# MCU.net
KiCad netlist of a schematic drawn in Altium Designer
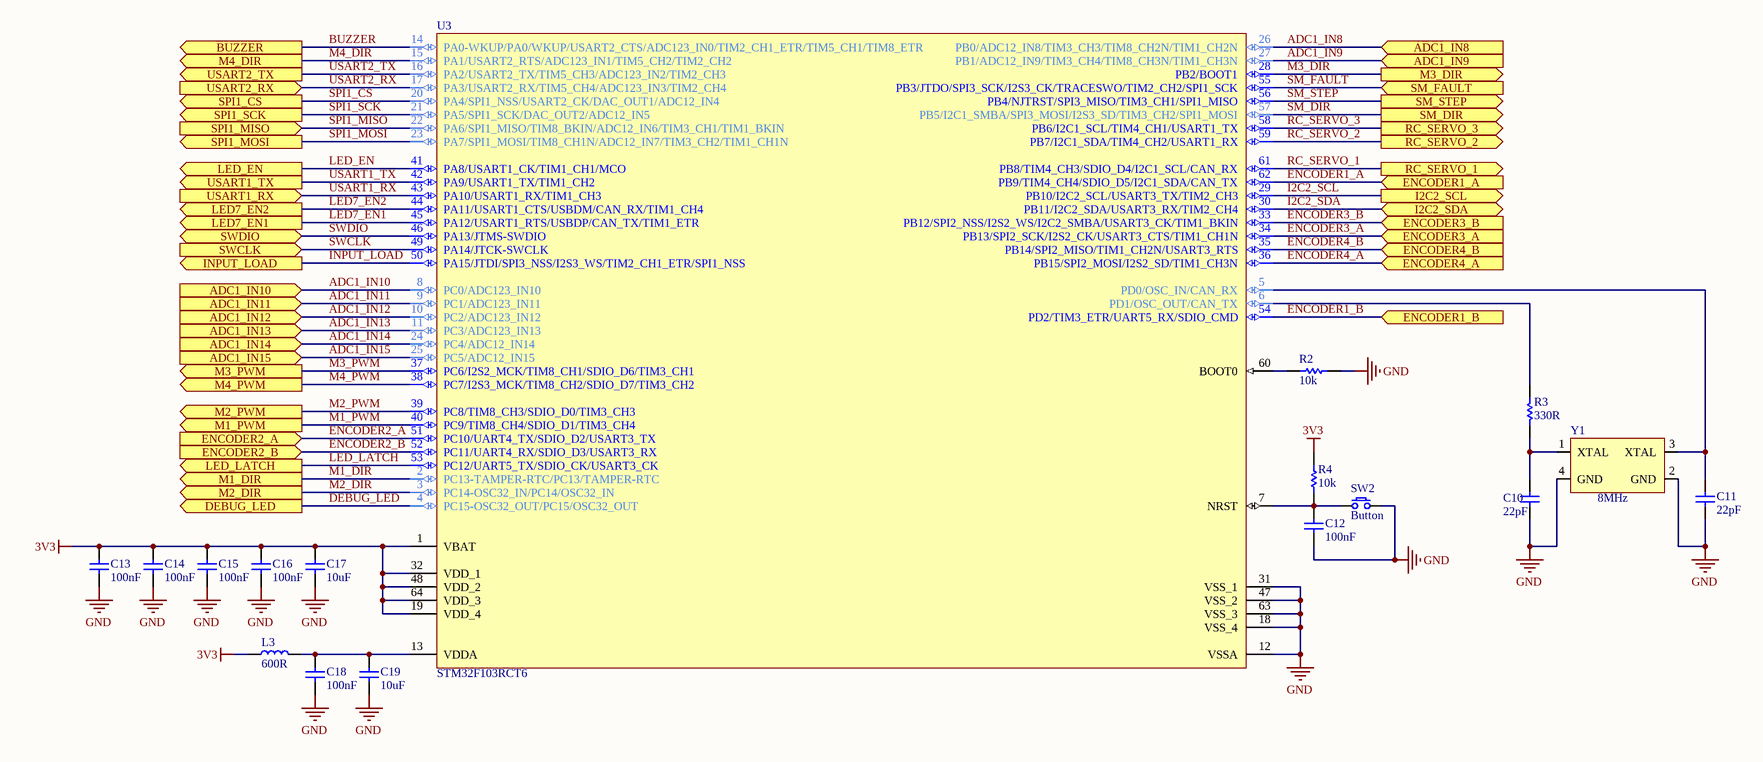
[diagram p0: MCU.SchDoc]

(export (version "E")
  (design (tool "Eeschema 10.0.6"))
  (components
    (comp (ref "C10")
      (value "22pF")
      (footprint "C 0603 (1608)")
      (description "Capacitor non-pol")
      (libsource (lib "BKIT4U_LIB") (part "Capacitor NP"))
    )
    (comp (ref "C11")
      (value "22pF")
      (footprint "C 0603 (1608)")
      (description "Capacitor non-pol")
      (libsource (lib "BKIT4U_LIB") (part "Capacitor NP"))
    )
    (comp (ref "C12")
      (value "100nF")
      (footprint "C 0603 (1608)")
      (description "Capacitor non-pol")
      (libsource (lib "BKIT4U_LIB") (part "Capacitor NP"))
    )
    (comp (ref "C13")
      (value "100nF")
      (footprint "C 0603 (1608)")
      (description "Capacitor non-pol")
      (libsource (lib "BKIT4U_LIB") (part "Capacitor NP"))
    )
    (comp (ref "C14")
      (value "100nF")
      (footprint "C 0603 (1608)")
      (description "Capacitor non-pol")
      (libsource (lib "BKIT4U_LIB") (part "Capacitor NP"))
    )
    (comp (ref "C15")
      (value "100nF")
      (footprint "C 0603 (1608)")
      (description "Capacitor non-pol")
      (libsource (lib "BKIT4U_LIB") (part "Capacitor NP"))
    )
    (comp (ref "C16")
      (value "100nF")
      (footprint "C 0603 (1608)")
      (description "Capacitor non-pol")
      (libsource (lib "BKIT4U_LIB") (part "Capacitor NP"))
    )
    (comp (ref "C17")
      (value "10uF")
      (footprint "C 0603 (1608)")
      (description "Capacitor non-pol")
      (libsource (lib "BKIT4U_LIB") (part "Capacitor NP"))
    )
    (comp (ref "C18")
      (value "100nF")
      (footprint "C 0603 (1608)")
      (description "Capacitor non-pol")
      (libsource (lib "BKIT4U_LIB") (part "Capacitor NP"))
    )
    (comp (ref "C19")
      (value "10uF")
      (footprint "C 0603 (1608)")
      (description "Capacitor non-pol")
      (libsource (lib "BKIT4U_LIB") (part "Capacitor NP"))
    )
    (comp (ref "L3")
      (value "600R")
      (footprint "L 0603 (1608)")
      (description "Inductor")
      (libsource (lib "BKIT4U_LIB") (part "Inductor"))
    )
    (comp (ref "R2")
      (value "10k")
      (footprint "R 0603 (1608)")
      (description "Resistor")
      (fields (field (name "PUBLISHER") "Altium Limited"))
      (libsource (lib "BKIT4U_LIB") (part "Resistor"))
    )
    (comp (ref "R3")
      (value "330R")
      (footprint "R 0603 (1608)")
      (description "Resistor")
      (fields (field (name "PUBLISHER") "Altium Limited"))
      (libsource (lib "BKIT4U_LIB") (part "Resistor"))
    )
    (comp (ref "R4")
      (value "10k")
      (footprint "R 0603 (1608)")
      (description "Resistor")
      (fields (field (name "PUBLISHER") "Altium Limited"))
      (libsource (lib "BKIT4U_LIB") (part "Resistor"))
    )
    (comp (ref "SW2")
      (value "Button")
      (footprint "SW/2/SMD - 6X6X5")
      (description "Tact switch 2 pin")
      (libsource (lib "BKIT4U_LIB") (part "SW SPST"))
    )
    (comp (ref "U3")
      (value "STM32F103RCT6")
      (footprint "LQFP64_N")
      (libsource (lib "BKIT4U_LIB") (part "STM32F103RCT6"))
    )
    (comp (ref "Y1")
      (value "8MHz")
      (footprint "Crystal SMD 4PIN 3225")
      (libsource (lib "BKIT4U_LIB") (part "Crystal 4pin"))
    )
  )
  (nets
    (net (code "1") (name "/ADC1_IN8") (class "Default")
      (node (ref "U3") (pin "26") (pinfunction "PB0/ADC12_IN8/TIM3_CH3/TIM8_CH2N/TIM1_CH2N_26") (pintype "bidirectional"))
    )
    (net (code "2") (name "/ADC1_IN9") (class "Default")
      (node (ref "U3") (pin "27") (pinfunction "PB1/ADC12_IN9/TIM3_CH4/TIM8_CH3N/TIM1_CH3N_27") (pintype "bidirectional"))
    )
    (net (code "3") (name "/ADC1_IN10") (class "Default")
      (node (ref "U3") (pin "8") (pinfunction "PC0/ADC123_IN10_8") (pintype "bidirectional"))
    )
    (net (code "4") (name "/ADC1_IN11") (class "Default")
      (node (ref "U3") (pin "9") (pinfunction "PC1/ADC123_IN11_9") (pintype "bidirectional"))
    )
    (net (code "5") (name "/ADC1_IN12") (class "Default")
      (node (ref "U3") (pin "10") (pinfunction "PC2/ADC123_IN12_10") (pintype "bidirectional"))
    )
    (net (code "6") (name "/ADC1_IN13") (class "Default")
      (node (ref "U3") (pin "11") (pinfunction "PC3/ADC123_IN13_11") (pintype "bidirectional"))
    )
    (net (code "7") (name "/ADC1_IN14") (class "Default")
      (node (ref "U3") (pin "24") (pinfunction "PC4/ADC12_IN14_24") (pintype "bidirectional"))
    )
    (net (code "8") (name "/ADC1_IN15") (class "Default")
      (node (ref "U3") (pin "25") (pinfunction "PC5/ADC12_IN15_25") (pintype "bidirectional"))
    )
    (net (code "9") (name "/BUZZER") (class "Default")
      (node (ref "U3") (pin "14") (pinfunction "PA0-WKUP/PA0/WKUP/USART2_CTS/ADC123_IN0/TIM2_CH1_ETR/TIM5_CH1/TIM8_ETR_14") (pintype "bidirectional"))
    )
    (net (code "10") (name "/DEBUG_LED") (class "Default")
      (node (ref "U3") (pin "4") (pinfunction "PC15-OSC32_OUT/PC15/OSC32_OUT_4") (pintype "bidirectional"))
    )
    (net (code "11") (name "/ENCODER1_A") (class "Default")
      (node (ref "U3") (pin "62") (pinfunction "PB9/TIM4_CH4/SDIO_D5/I2C1_SDA/CAN_TX_62") (pintype "bidirectional"))
    )
    (net (code "12") (name "/ENCODER1_B") (class "Default")
      (node (ref "U3") (pin "54") (pinfunction "PD2/TIM3_ETR/UART5_RX/SDIO_CMD_54") (pintype "bidirectional"))
    )
    (net (code "13") (name "/ENCODER2_A") (class "Default")
      (node (ref "U3") (pin "51") (pinfunction "PC10/UART4_TX/SDIO_D2/USART3_TX_51") (pintype "bidirectional"))
    )
    (net (code "14") (name "/ENCODER2_B") (class "Default")
      (node (ref "U3") (pin "52") (pinfunction "PC11/UART4_RX/SDIO_D3/USART3_RX_52") (pintype "bidirectional"))
    )
    (net (code "15") (name "/ENCODER3_A") (class "Default")
      (node (ref "U3") (pin "34") (pinfunction "PB13/SPI2_SCK/I2S2_CK/USART3_CTS/TIM1_CH1N_34") (pintype "bidirectional"))
    )
    (net (code "16") (name "/ENCODER3_B") (class "Default")
      (node (ref "U3") (pin "33") (pinfunction "PB12/SPI2_NSS/I2S2_WS/I2C2_SMBA/USART3_CK/TIM1_BKIN_33") (pintype "bidirectional"))
    )
    (net (code "17") (name "/ENCODER4_A") (class "Default")
      (node (ref "U3") (pin "36") (pinfunction "PB15/SPI2_MOSI/I2S2_SD/TIM1_CH3N_36") (pintype "bidirectional"))
    )
    (net (code "18") (name "/ENCODER4_B") (class "Default")
      (node (ref "U3") (pin "35") (pinfunction "PB14/SPI2_MISO/TIM1_CH2N/USART3_RTS_35") (pintype "bidirectional"))
    )
    (net (code "19") (name "/I2C2_SCL") (class "Default")
      (node (ref "U3") (pin "29") (pinfunction "PB10/I2C2_SCL/USART3_TX/TIM2_CH3_29") (pintype "bidirectional"))
    )
    (net (code "20") (name "/I2C2_SDA") (class "Default")
      (node (ref "U3") (pin "30") (pinfunction "PB11/I2C2_SDA/USART3_RX/TIM2_CH4_30") (pintype "bidirectional"))
    )
    (net (code "21") (name "/INPUT_LOAD") (class "Default")
      (node (ref "U3") (pin "50") (pinfunction "PA15/JTDI/SPI3_NSS/I2S3_WS/TIM2_CH1_ETR/SPI1_NSS_50") (pintype "bidirectional"))
    )
    (net (code "22") (name "/LED7_EN1") (class "Default")
      (node (ref "U3") (pin "45") (pinfunction "PA12/USART1_RTS/USBDP/CAN_TX/TIM1_ETR_45") (pintype "bidirectional"))
    )
    (net (code "23") (name "/LED7_EN2") (class "Default")
      (node (ref "U3") (pin "44") (pinfunction "PA11/USART1_CTS/USBDM/CAN_RX/TIM1_CH4_44") (pintype "bidirectional"))
    )
    (net (code "24") (name "/LED_EN") (class "Default")
      (node (ref "U3") (pin "41") (pinfunction "PA8/USART1_CK/TIM1_CH1/MCO_41") (pintype "bidirectional"))
    )
    (net (code "25") (name "/LED_LATCH") (class "Default")
      (node (ref "U3") (pin "53") (pinfunction "PC12/UART5_TX/SDIO_CK/USART3_CK_53") (pintype "bidirectional"))
    )
    (net (code "26") (name "/M1_DIR") (class "Default")
      (node (ref "U3") (pin "2") (pinfunction "PC13-TAMPER-RTC/PC13/TAMPER-RTC_2") (pintype "bidirectional"))
    )
    (net (code "27") (name "/M1_PWM") (class "Default")
      (node (ref "U3") (pin "40") (pinfunction "PC9/TIM8_CH4/SDIO_D1/TIM3_CH4_40") (pintype "bidirectional"))
    )
    (net (code "28") (name "/M2_DIR") (class "Default")
      (node (ref "U3") (pin "3") (pinfunction "PC14-OSC32_IN/PC14/OSC32_IN_3") (pintype "bidirectional"))
    )
    (net (code "29") (name "/M2_PWM") (class "Default")
      (node (ref "U3") (pin "39") (pinfunction "PC8/TIM8_CH3/SDIO_D0/TIM3_CH3_39") (pintype "bidirectional"))
    )
    (net (code "30") (name "/M3_DIR") (class "Default")
      (node (ref "U3") (pin "28") (pinfunction "PB2/BOOT1_28") (pintype "bidirectional"))
    )
    (net (code "31") (name "/M3_PWM") (class "Default")
      (node (ref "U3") (pin "37") (pinfunction "PC6/I2S2_MCK/TIM8_CH1/SDIO_D6/TIM3_CH1_37") (pintype "bidirectional"))
    )
    (net (code "32") (name "/M4_DIR") (class "Default")
      (node (ref "U3") (pin "15") (pinfunction "PA1/USART2_RTS/ADC123_IN1/TIM5_CH2/TIM2_CH2_15") (pintype "bidirectional"))
    )
    (net (code "33") (name "/M4_PWM") (class "Default")
      (node (ref "U3") (pin "38") (pinfunction "PC7/I2S3_MCK/TIM8_CH2/SDIO_D7/TIM3_CH2_38") (pintype "bidirectional"))
    )
    (net (code "34") (name "/RC_SERVO_1") (class "Default")
      (node (ref "U3") (pin "61") (pinfunction "PB8/TIM4_CH3/SDIO_D4/I2C1_SCL/CAN_RX_61") (pintype "bidirectional"))
    )
    (net (code "35") (name "/RC_SERVO_2") (class "Default")
      (node (ref "U3") (pin "59") (pinfunction "PB7/I2C1_SDA/TIM4_CH2/USART1_RX_59") (pintype "bidirectional"))
    )
    (net (code "36") (name "/RC_SERVO_3") (class "Default")
      (node (ref "U3") (pin "58") (pinfunction "PB6/I2C1_SCL/TIM4_CH1/USART1_TX_58") (pintype "bidirectional"))
    )
    (net (code "37") (name "/SM_DIR") (class "Default")
      (node (ref "U3") (pin "57") (pinfunction "PB5/I2C1_SMBA/SPI3_MOSI/I2S3_SD/TIM3_CH2/SPI1_MOSI_57") (pintype "bidirectional"))
    )
    (net (code "38") (name "/SM_FAULT") (class "Default")
      (node (ref "U3") (pin "55") (pinfunction "PB3/JTDO/SPI3_SCK/I2S3_CK/TRACESWO/TIM2_CH2/SPI1_SCK_55") (pintype "bidirectional"))
    )
    (net (code "39") (name "/SM_STEP") (class "Default")
      (node (ref "U3") (pin "56") (pinfunction "PB4/NJTRST/SPI3_MISO/TIM3_CH1/SPI1_MISO_56") (pintype "bidirectional"))
    )
    (net (code "40") (name "/SPI1_CS") (class "Default")
      (node (ref "U3") (pin "20") (pinfunction "PA4/SPI1_NSS/USART2_CK/DAC_OUT1/ADC12_IN4_20") (pintype "bidirectional"))
    )
    (net (code "41") (name "/SPI1_MISO") (class "Default")
      (node (ref "U3") (pin "22") (pinfunction "PA6/SPI1_MISO/TIM8_BKIN/ADC12_IN6/TIM3_CH1/TIM1_BKIN_22") (pintype "bidirectional"))
    )
    (net (code "42") (name "/SPI1_MOSI") (class "Default")
      (node (ref "U3") (pin "23") (pinfunction "PA7/SPI1_MOSI/TIM8_CH1N/ADC12_IN7/TIM3_CH2/TIM1_CH1N_23") (pintype "bidirectional"))
    )
    (net (code "43") (name "/SPI1_SCK") (class "Default")
      (node (ref "U3") (pin "21") (pinfunction "PA5/SPI1_SCK/DAC_OUT2/ADC12_IN5_21") (pintype "bidirectional"))
    )
    (net (code "44") (name "/SWCLK") (class "Default")
      (node (ref "U3") (pin "49") (pinfunction "PA14/JTCK-SWCLK_49") (pintype "bidirectional"))
    )
    (net (code "45") (name "/SWDIO") (class "Default")
      (node (ref "U3") (pin "46") (pinfunction "PA13/JTMS-SWDIO_46") (pintype "bidirectional"))
    )
    (net (code "46") (name "/USART1_RX") (class "Default")
      (node (ref "U3") (pin "43") (pinfunction "PA10/USART1_RX/TIM1_CH3_43") (pintype "bidirectional"))
    )
    (net (code "47") (name "/USART1_TX") (class "Default")
      (node (ref "U3") (pin "42") (pinfunction "PA9/USART1_TX/TIM1_CH2_42") (pintype "bidirectional"))
    )
    (net (code "48") (name "/USART2_RX") (class "Default")
      (node (ref "U3") (pin "17") (pinfunction "PA3/USART2_RX/TIM5_CH4/ADC123_IN3/TIM2_CH4_17") (pintype "bidirectional"))
    )
    (net (code "49") (name "/USART2_TX") (class "Default")
      (node (ref "U3") (pin "16") (pinfunction "PA2/USART2_TX/TIM5_CH3/ADC123_IN2/TIM2_CH3_16") (pintype "bidirectional"))
    )
    (net (code "50") (name "3V3") (class "Default")
      (node (ref "C13") (pin "1") (pinfunction "1_1") (pintype "passive"))
      (node (ref "C14") (pin "1") (pinfunction "1_1") (pintype "passive"))
      (node (ref "C15") (pin "1") (pinfunction "1_1") (pintype "passive"))
      (node (ref "C16") (pin "1") (pinfunction "1_1") (pintype "passive"))
      (node (ref "C17") (pin "1") (pinfunction "1_1") (pintype "passive"))
      (node (ref "L3") (pin "2") (pinfunction "2_2") (pintype "passive"))
      (node (ref "R4") (pin "1") (pinfunction "1_1") (pintype "passive"))
      (node (ref "U3") (pin "1") (pinfunction "VBAT_1") (pintype "power_in"))
      (node (ref "U3") (pin "19") (pinfunction "VDD_4_19") (pintype "power_in"))
      (node (ref "U3") (pin "32") (pinfunction "VDD_1_32") (pintype "power_in"))
      (node (ref "U3") (pin "48") (pinfunction "VDD_2_48") (pintype "power_in"))
      (node (ref "U3") (pin "64") (pinfunction "VDD_3_64") (pintype "power_in"))
    )
    (net (code "51") (name "GND") (class "Default")
      (node (ref "C10") (pin "2") (pinfunction "2_2") (pintype "passive"))
      (node (ref "C11") (pin "2") (pinfunction "2_2") (pintype "passive"))
      (node (ref "C12") (pin "2") (pinfunction "2_2") (pintype "passive"))
      (node (ref "C13") (pin "2") (pinfunction "2_2") (pintype "passive"))
      (node (ref "C14") (pin "2") (pinfunction "2_2") (pintype "passive"))
      (node (ref "C15") (pin "2") (pinfunction "2_2") (pintype "passive"))
      (node (ref "C16") (pin "2") (pinfunction "2_2") (pintype "passive"))
      (node (ref "C17") (pin "2") (pinfunction "2_2") (pintype "passive"))
      (node (ref "C18") (pin "2") (pinfunction "2_2") (pintype "passive"))
      (node (ref "C19") (pin "2") (pinfunction "2_2") (pintype "passive"))
      (node (ref "R2") (pin "1") (pinfunction "1_1") (pintype "passive"))
      (node (ref "SW2") (pin "2") (pinfunction "2_2") (pintype "passive"))
      (node (ref "U3") (pin "12") (pinfunction "VSSA_12") (pintype "power_in"))
      (node (ref "U3") (pin "18") (pinfunction "VSS_4_18") (pintype "power_in"))
      (node (ref "U3") (pin "31") (pinfunction "VSS_1_31") (pintype "power_in"))
      (node (ref "U3") (pin "47") (pinfunction "VSS_2_47") (pintype "power_in"))
      (node (ref "U3") (pin "63") (pinfunction "VSS_3_63") (pintype "power_in"))
      (node (ref "Y1") (pin "2") (pinfunction "GND_2") (pintype "passive"))
      (node (ref "Y1") (pin "4") (pinfunction "GND_4") (pintype "passive"))
    )
    (net (code "52") (name "Net-(C10-Pad1)") (class "Default")
      (node (ref "C10") (pin "1") (pinfunction "1_1") (pintype "passive"))
      (node (ref "R3") (pin "1") (pinfunction "1_1") (pintype "passive"))
      (node (ref "Y1") (pin "1") (pinfunction "XTAL_1") (pintype "passive"))
    )
    (net (code "53") (name "Net-(U3-BOOT0)") (class "Default")
      (node (ref "R2") (pin "2") (pinfunction "2_2") (pintype "passive"))
      (node (ref "U3") (pin "60") (pinfunction "BOOT0_60") (pintype "input"))
    )
    (net (code "54") (name "Net-(U3-NRST)") (class "Default")
      (node (ref "C12") (pin "1") (pinfunction "1_1") (pintype "passive"))
      (node (ref "R4") (pin "2") (pinfunction "2_2") (pintype "passive"))
      (node (ref "SW2") (pin "1") (pinfunction "1_1") (pintype "passive"))
      (node (ref "U3") (pin "7") (pinfunction "NRST_7") (pintype "bidirectional"))
    )
    (net (code "55") (name "Net-(U3-PD0{slash}OSC_IN{slash}CAN_RX)") (class "Default")
      (node (ref "C11") (pin "1") (pinfunction "1_1") (pintype "passive"))
      (node (ref "U3") (pin "5") (pinfunction "PD0/OSC_IN/CAN_RX_5") (pintype "bidirectional"))
      (node (ref "Y1") (pin "3") (pinfunction "XTAL_3") (pintype "passive"))
    )
    (net (code "56") (name "Net-(U3-PD1{slash}OSC_OUT{slash}CAN_TX)") (class "Default")
      (node (ref "R3") (pin "2") (pinfunction "2_2") (pintype "passive"))
      (node (ref "U3") (pin "6") (pinfunction "PD1/OSC_OUT/CAN_TX_6") (pintype "bidirectional"))
    )
    (net (code "57") (name "Net-(U3-VDDA)") (class "Default")
      (node (ref "C18") (pin "1") (pinfunction "1_1") (pintype "passive"))
      (node (ref "C19") (pin "1") (pinfunction "1_1") (pintype "passive"))
      (node (ref "L3") (pin "1") (pinfunction "1_1") (pintype "passive"))
      (node (ref "U3") (pin "13") (pinfunction "VDDA_13") (pintype "power_in"))
    )
  )
)
